# ProtoStack_H750VBT.net
KiCad netlist of a schematic drawn in Altium Designer
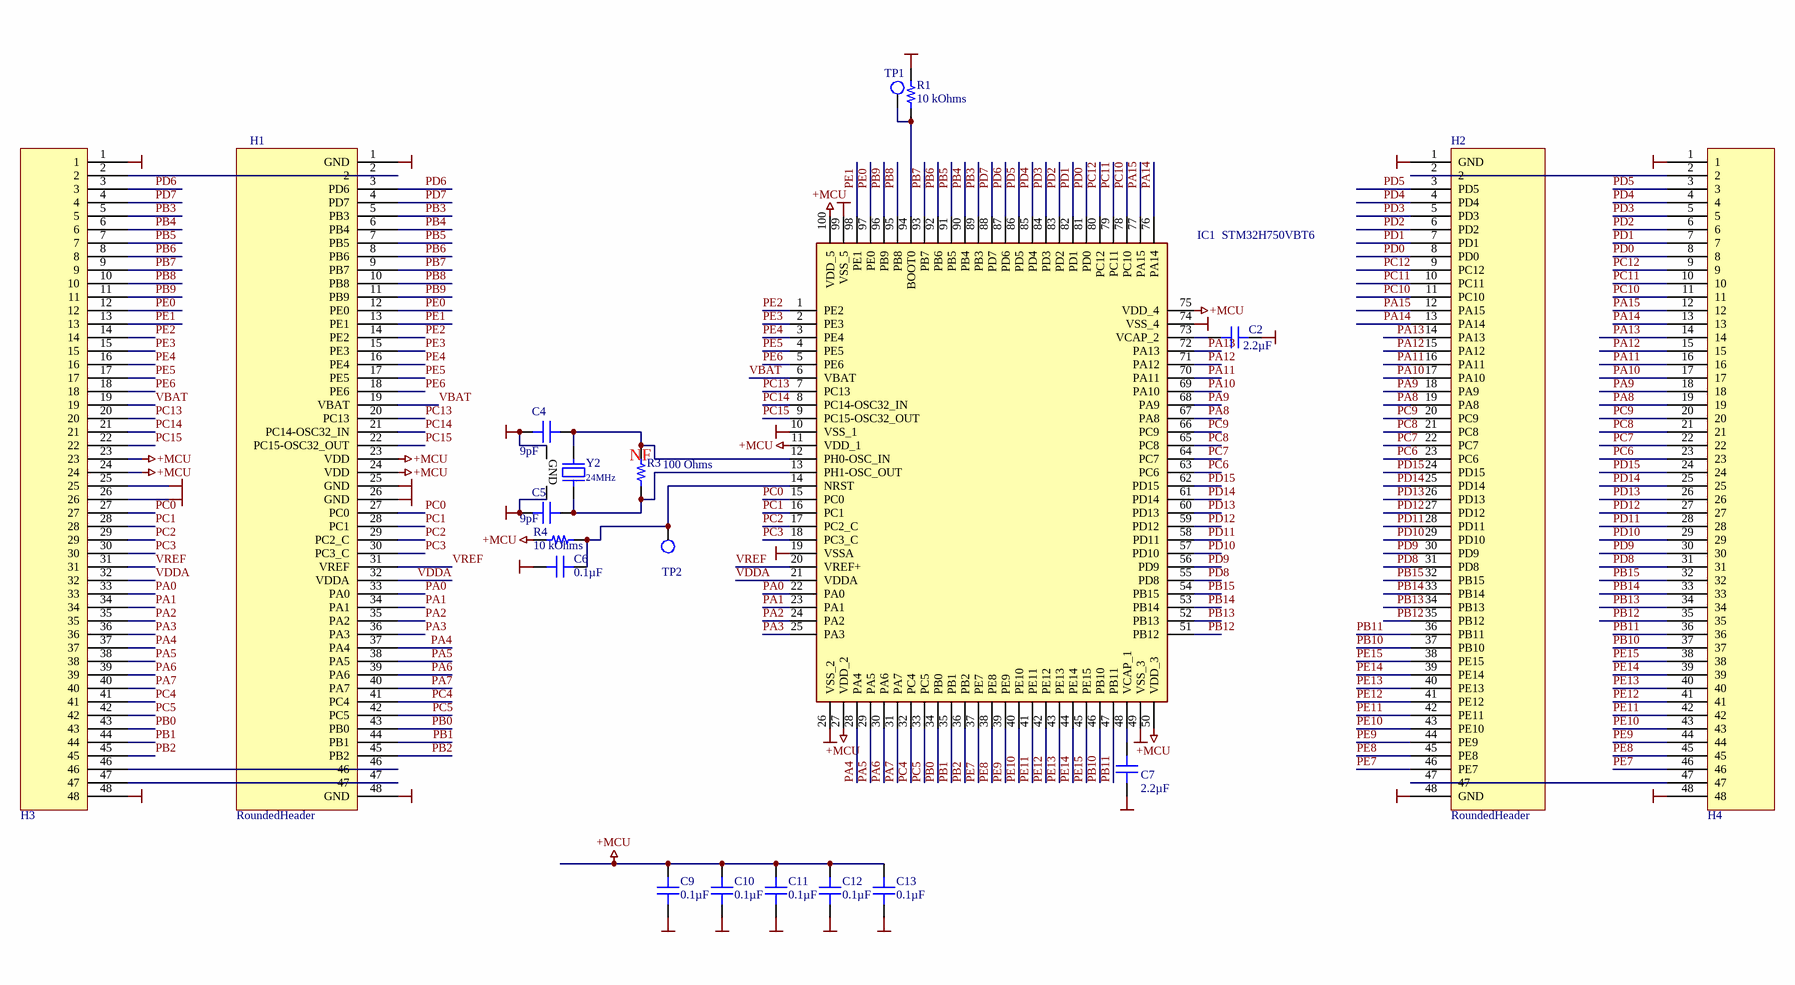
[diagram p0: ProtoStack_H750VBT.SchDoc]

(export (version "E")
  (design (tool "Eeschema 10.0.6"))
  (components
    (comp (ref "C2")
      (value "2.2µF")
      (footprint "CAP 0805_2012")
      (description "CAP CER 2.2UF 10V X7R 0805")
      (fields (field (name "PART NUMBER") "C0805C225K8RACTU") (field (name "MANUFACTURER") "KEMET"))
      (libsource (lib "Celestial Altium Library - altium_library") (part "Capacitor"))
    )
    (comp (ref "C4")
      (value "9pF")
      (footprint "CAP 0805_2012")
      (description "CAP CER 9PF 250V C0G/NP0 0805")
      (fields (field (name "PART NUMBER") "CBR08C909CAGAC") (field (name "MANUFACTURER") "KEMET"))
      (libsource (lib "Celestial Altium Library - altium_library") (part "Capacitor"))
    )
    (comp (ref "C5")
      (value "9pF")
      (footprint "CAP 0805_2012")
      (description "CAP CER 9PF 250V C0G/NP0 0805")
      (fields (field (name "PART NUMBER") "CBR08C909CAGAC") (field (name "MANUFACTURER") "KEMET"))
      (libsource (lib "Celestial Altium Library - altium_library") (part "Capacitor"))
    )
    (comp (ref "C6")
      (value "0.1µF")
      (footprint "CAP 0402_1005")
      (description "CAP CER 0.1UF 16V X7R 0402")
      (fields (field (name "PART NUMBER") "C0402C104K4RACAUTO") (field (name "MANUFACTURER") "KEMET"))
      (libsource (lib "Celestial Altium Library - altium_library") (part "Capacitor"))
    )
    (comp (ref "C7")
      (value "2.2µF")
      (footprint "CAP 0805_2012")
      (description "CAP CER 2.2UF 10V X7R 0805")
      (fields (field (name "PART NUMBER") "C0805C225K8RACTU") (field (name "MANUFACTURER") "KEMET"))
      (libsource (lib "Celestial Altium Library - altium_library") (part "Capacitor"))
    )
    (comp (ref "C9")
      (value "0.1µF")
      (footprint "CAP 0402_1005")
      (description "CAP CER 0.1UF 16V X7R 0402")
      (fields (field (name "PART NUMBER") "C0402C104K4RACAUTO") (field (name "MANUFACTURER") "KEMET"))
      (libsource (lib "Celestial Altium Library - altium_library") (part "Capacitor"))
    )
    (comp (ref "C10")
      (value "0.1µF")
      (footprint "CAP 0402_1005")
      (description "CAP CER 0.1UF 16V X7R 0402")
      (fields (field (name "PART NUMBER") "C0402C104K4RACAUTO") (field (name "MANUFACTURER") "KEMET"))
      (libsource (lib "Celestial Altium Library - altium_library") (part "Capacitor"))
    )
    (comp (ref "C11")
      (value "0.1µF")
      (footprint "CAP 0402_1005")
      (description "CAP CER 0.1UF 16V X7R 0402")
      (fields (field (name "PART NUMBER") "C0402C104K4RACAUTO") (field (name "MANUFACTURER") "KEMET"))
      (libsource (lib "Celestial Altium Library - altium_library") (part "Capacitor"))
    )
    (comp (ref "C12")
      (value "0.1µF")
      (footprint "CAP 0402_1005")
      (description "CAP CER 0.1UF 16V X7R 0402")
      (fields (field (name "PART NUMBER") "C0402C104K4RACAUTO") (field (name "MANUFACTURER") "KEMET"))
      (libsource (lib "Celestial Altium Library - altium_library") (part "Capacitor"))
    )
    (comp (ref "C13")
      (value "0.1µF")
      (footprint "CAP 0402_1005")
      (description "CAP CER 0.1UF 16V X7R 0402")
      (fields (field (name "PART NUMBER") "C0402C104K4RACAUTO") (field (name "MANUFACTURER") "KEMET"))
      (libsource (lib "Celestial Altium Library - altium_library") (part "Capacitor"))
    )
    (comp (ref "H1")
      (value "RoundedHeader")
      (footprint "ProtoStack_H750VBT:HeaderDtack_48")
      (libsource (lib "ProtoStack_H750VBT") (part "HeaderStack_48_H7VB50_L"))
    )
    (comp (ref "H2")
      (value "RoundedHeader")
      (footprint "ProtoStack_H750VBT:HeaderDtack_48")
      (libsource (lib "ProtoStack_H750VBT") (part "HeaderStack_48_H7VB50_R"))
    )
    (comp (ref "H3")
      (value "male pin header")
      (footprint "ProtoStack_H750VBT:Header_48")
      (libsource (lib "") (part "Header_48_1"))
    )
    (comp (ref "H4")
      (value "male pin header")
      (footprint "ProtoStack_H750VBT:Header_48")
      (libsource (lib "ProtoStack_H750VBT") (part "Header_48"))
    )
    (comp (ref "IC1")
      (value "STM32H750VBT6")
      (footprint "ProtoStack_H750VBT:QFP50P1600X1600X160-100N")
      (description "Integrated Circuit")
      (fields (field (name "MOUSER PART NUMBER") "511-STM32H750VBT6"))
      (libsource (lib "ProtoStack_H750VBT") (part "STM32H750VBT6"))
    )
    (comp (ref "R1")
      (value "10 kOhms")
      (footprint "RES 0603_1608")
      (description "RES SMD 10K OHM 1% 1/10W 0603")
      (fields (field (name "PART NUMBER") "RT0603FRE0710KL") (field (name "MANUFACTURER") "Yageo"))
      (libsource (lib "Celestial Altium Library - altium_library") (part "Resistor"))
    )
    (comp (ref "R3")
      (value "100 Ohms")
      (footprint "RES 0402_1005")
      (description "RES SMD 100 OHM 1% 1/16W 0402")
      (fields (field (name "PART NUMBER") "RT0402FRE07100RL") (field (name "MANUFACTURER") "Yageo"))
      (libsource (lib "Celestial Altium Library - altium_library") (part "Resistor"))
    )
    (comp (ref "R4")
      (value "10 kOhms")
      (footprint "RES 0603_1608")
      (description "RES SMD 10K OHM 1% 1/10W 0603")
      (fields (field (name "PART NUMBER") "RT0603FRE0710KL") (field (name "MANUFACTURER") "Yageo"))
      (libsource (lib "Celestial Altium Library - altium_library") (part "Resistor"))
    )
    (comp (ref "TP1")
      (value "TestPoint")
      (footprint "ProtoStack_H750VBT:TESTPOINT_VIA")
      (libsource (lib "ProtoStack_H750VBT") (part "TestPoint"))
    )
    (comp (ref "TP2")
      (value "NRST")
      (footprint "ProtoStack_H750VBT:TESTPOINT")
      (libsource (lib "ProtoStack_H750VBT") (part "TestPoint"))
    )
    (comp (ref "Y2")
      (value "24MHz")
      (footprint "NDK NX3225SA")
      (description "CRYSTAL 24MHZ 9PF SMD")
      (fields
        (field (name "PART NUMBER") "NX3225SA-24MHZ-EXS00A-CS07532")
        (field (name "MANUFACTURER") "NDK America, Inc.")
      )
      (libsource (lib "Celestial Altium Library - altium_library") (part "NDK Crystal NX3225SA"))
    )
  )
  (nets
    (net (code "1") (name "+MCU") (class "Default")
      (node (ref "C10") (pin "1") (pinfunction "1_1") (pintype "passive"))
      (node (ref "C11") (pin "1") (pinfunction "1_1") (pintype "passive"))
      (node (ref "C12") (pin "1") (pinfunction "1_1") (pintype "passive"))
      (node (ref "C13") (pin "1") (pinfunction "1_1") (pintype "passive"))
      (node (ref "C9") (pin "1") (pinfunction "1_1") (pintype "passive"))
      (node (ref "H1") (pin "23") (pinfunction "VDD_23") (pintype "passive"))
      (node (ref "H1") (pin "24") (pinfunction "VDD_24") (pintype "passive"))
      (node (ref "H3") (pin "23") (pinfunction "23_23") (pintype "passive"))
      (node (ref "H3") (pin "24") (pinfunction "24_24") (pintype "passive"))
      (node (ref "IC1") (pin "100") (pinfunction "VDD_5_100") (pintype "passive"))
      (node (ref "IC1") (pin "11") (pinfunction "VDD_1_11") (pintype "passive"))
      (node (ref "IC1") (pin "27") (pinfunction "VDD_2_27") (pintype "passive"))
      (node (ref "IC1") (pin "50") (pinfunction "VDD_3_50") (pintype "passive"))
      (node (ref "IC1") (pin "75") (pinfunction "VDD_4_75") (pintype "passive"))
      (node (ref "R4") (pin "1") (pinfunction "1_1") (pintype "passive"))
    )
    (net (code "2") (name "/PA0") (class "Default")
      (node (ref "H1") (pin "33") (pinfunction "PA0_33") (pintype "passive"))
      (node (ref "H3") (pin "33") (pinfunction "33_33") (pintype "passive"))
      (node (ref "IC1") (pin "22") (pinfunction "PA0_22") (pintype "passive"))
    )
    (net (code "3") (name "/PA1") (class "Default")
      (node (ref "H1") (pin "34") (pinfunction "PA1_34") (pintype "passive"))
      (node (ref "H3") (pin "34") (pinfunction "34_34") (pintype "passive"))
      (node (ref "IC1") (pin "23") (pinfunction "PA1_23") (pintype "passive"))
    )
    (net (code "4") (name "/PA2") (class "Default")
      (node (ref "H1") (pin "35") (pinfunction "PA2_35") (pintype "passive"))
      (node (ref "H3") (pin "35") (pinfunction "35_35") (pintype "passive"))
      (node (ref "IC1") (pin "24") (pinfunction "PA2_24") (pintype "passive"))
    )
    (net (code "5") (name "/PA3") (class "Default")
      (node (ref "H1") (pin "36") (pinfunction "PA3_36") (pintype "passive"))
      (node (ref "H3") (pin "36") (pinfunction "36_36") (pintype "passive"))
      (node (ref "IC1") (pin "25") (pinfunction "PA3_25") (pintype "passive"))
    )
    (net (code "6") (name "/PA4") (class "Default")
      (node (ref "H1") (pin "37") (pinfunction "PA4_37") (pintype "passive"))
      (node (ref "H3") (pin "37") (pinfunction "37_37") (pintype "passive"))
      (node (ref "IC1") (pin "28") (pinfunction "PA4_28") (pintype "passive"))
    )
    (net (code "7") (name "/PA5") (class "Default")
      (node (ref "H1") (pin "38") (pinfunction "PA5_38") (pintype "passive"))
      (node (ref "H3") (pin "38") (pinfunction "38_38") (pintype "passive"))
      (node (ref "IC1") (pin "29") (pinfunction "PA5_29") (pintype "passive"))
    )
    (net (code "8") (name "/PA6") (class "Default")
      (node (ref "H1") (pin "39") (pinfunction "PA6_39") (pintype "passive"))
      (node (ref "H3") (pin "39") (pinfunction "39_39") (pintype "passive"))
      (node (ref "IC1") (pin "30") (pinfunction "PA6_30") (pintype "passive"))
    )
    (net (code "9") (name "/PA7") (class "Default")
      (node (ref "H1") (pin "40") (pinfunction "PA7_40") (pintype "passive"))
      (node (ref "H3") (pin "40") (pinfunction "40_40") (pintype "passive"))
      (node (ref "IC1") (pin "31") (pinfunction "PA7_31") (pintype "passive"))
    )
    (net (code "10") (name "/PA8") (class "Default")
      (node (ref "H2") (pin "19") (pinfunction "PA8_19") (pintype "passive"))
      (node (ref "H4") (pin "19") (pinfunction "19_19") (pintype "passive"))
      (node (ref "IC1") (pin "67") (pinfunction "PA8_67") (pintype "passive"))
    )
    (net (code "11") (name "/PA9") (class "Default")
      (node (ref "H2") (pin "18") (pinfunction "PA9_18") (pintype "passive"))
      (node (ref "H4") (pin "18") (pinfunction "18_18") (pintype "passive"))
      (node (ref "IC1") (pin "68") (pinfunction "PA9_68") (pintype "passive"))
    )
    (net (code "12") (name "/PA10") (class "Default")
      (node (ref "H2") (pin "17") (pinfunction "PA10_17") (pintype "passive"))
      (node (ref "H4") (pin "17") (pinfunction "17_17") (pintype "passive"))
      (node (ref "IC1") (pin "69") (pinfunction "PA10_69") (pintype "passive"))
    )
    (net (code "13") (name "/PA11") (class "Default")
      (node (ref "H2") (pin "16") (pinfunction "PA11_16") (pintype "passive"))
      (node (ref "H4") (pin "16") (pinfunction "16_16") (pintype "passive"))
      (node (ref "IC1") (pin "70") (pinfunction "PA11_70") (pintype "passive"))
    )
    (net (code "14") (name "/PA12") (class "Default")
      (node (ref "H2") (pin "15") (pinfunction "PA12_15") (pintype "passive"))
      (node (ref "H4") (pin "15") (pinfunction "15_15") (pintype "passive"))
      (node (ref "IC1") (pin "71") (pinfunction "PA12_71") (pintype "passive"))
    )
    (net (code "15") (name "/PA13") (class "Default")
      (node (ref "H2") (pin "14") (pinfunction "PA13_14") (pintype "passive"))
      (node (ref "H4") (pin "14") (pinfunction "14_14") (pintype "passive"))
      (node (ref "IC1") (pin "72") (pinfunction "PA13_72") (pintype "passive"))
    )
    (net (code "16") (name "/PA14") (class "Default")
      (node (ref "H2") (pin "13") (pinfunction "PA14_13") (pintype "passive"))
      (node (ref "H4") (pin "13") (pinfunction "13_13") (pintype "passive"))
      (node (ref "IC1") (pin "76") (pinfunction "PA14_76") (pintype "passive"))
    )
    (net (code "17") (name "/PA15") (class "Default")
      (node (ref "H2") (pin "12") (pinfunction "PA15_12") (pintype "passive"))
      (node (ref "H4") (pin "12") (pinfunction "12_12") (pintype "passive"))
      (node (ref "IC1") (pin "77") (pinfunction "PA15_77") (pintype "passive"))
    )
    (net (code "18") (name "/PB0") (class "Default")
      (node (ref "H1") (pin "43") (pinfunction "PB0_43") (pintype "passive"))
      (node (ref "H3") (pin "43") (pinfunction "43_43") (pintype "passive"))
      (node (ref "IC1") (pin "34") (pinfunction "PB0_34") (pintype "passive"))
    )
    (net (code "19") (name "/PB1") (class "Default")
      (node (ref "H1") (pin "44") (pinfunction "PB1_44") (pintype "passive"))
      (node (ref "H3") (pin "44") (pinfunction "44_44") (pintype "passive"))
      (node (ref "IC1") (pin "35") (pinfunction "PB1_35") (pintype "passive"))
    )
    (net (code "20") (name "/PB2") (class "Default")
      (node (ref "H1") (pin "45") (pinfunction "PB2_45") (pintype "passive"))
      (node (ref "H3") (pin "45") (pinfunction "45_45") (pintype "passive"))
      (node (ref "IC1") (pin "36") (pinfunction "PB2_36") (pintype "passive"))
    )
    (net (code "21") (name "/PB3") (class "Default")
      (node (ref "H1") (pin "5") (pinfunction "PB3_5") (pintype "passive"))
      (node (ref "H3") (pin "5") (pinfunction "5_5") (pintype "passive"))
      (node (ref "IC1") (pin "89") (pinfunction "PB3_89") (pintype "passive"))
    )
    (net (code "22") (name "/PB4") (class "Default")
      (node (ref "H1") (pin "6") (pinfunction "PB4_6") (pintype "passive"))
      (node (ref "H3") (pin "6") (pinfunction "6_6") (pintype "passive"))
      (node (ref "IC1") (pin "90") (pinfunction "PB4_90") (pintype "passive"))
    )
    (net (code "23") (name "/PB5") (class "Default")
      (node (ref "H1") (pin "7") (pinfunction "PB5_7") (pintype "passive"))
      (node (ref "H3") (pin "7") (pinfunction "7_7") (pintype "passive"))
      (node (ref "IC1") (pin "91") (pinfunction "PB5_91") (pintype "passive"))
    )
    (net (code "24") (name "/PB6") (class "Default")
      (node (ref "H1") (pin "8") (pinfunction "PB6_8") (pintype "passive"))
      (node (ref "H3") (pin "8") (pinfunction "8_8") (pintype "passive"))
      (node (ref "IC1") (pin "92") (pinfunction "PB6_92") (pintype "passive"))
    )
    (net (code "25") (name "/PB7") (class "Default")
      (node (ref "H1") (pin "9") (pinfunction "PB7_9") (pintype "passive"))
      (node (ref "H3") (pin "9") (pinfunction "9_9") (pintype "passive"))
      (node (ref "IC1") (pin "93") (pinfunction "PB7_93") (pintype "passive"))
    )
    (net (code "26") (name "/PB8") (class "Default")
      (node (ref "H1") (pin "10") (pinfunction "PB8_10") (pintype "passive"))
      (node (ref "H3") (pin "10") (pinfunction "10_10") (pintype "passive"))
      (node (ref "IC1") (pin "95") (pinfunction "PB8_95") (pintype "passive"))
    )
    (net (code "27") (name "/PB9") (class "Default")
      (node (ref "H1") (pin "11") (pinfunction "PB9_11") (pintype "passive"))
      (node (ref "H3") (pin "11") (pinfunction "11_11") (pintype "passive"))
      (node (ref "IC1") (pin "96") (pinfunction "PB9_96") (pintype "passive"))
    )
    (net (code "28") (name "/PB10") (class "Default")
      (node (ref "H2") (pin "37") (pinfunction "PB10_37") (pintype "passive"))
      (node (ref "H4") (pin "37") (pinfunction "37_37") (pintype "passive"))
      (node (ref "IC1") (pin "46") (pinfunction "PB10_46") (pintype "passive"))
    )
    (net (code "29") (name "/PB11") (class "Default")
      (node (ref "H2") (pin "36") (pinfunction "PB11_36") (pintype "passive"))
      (node (ref "H4") (pin "36") (pinfunction "36_36") (pintype "passive"))
      (node (ref "IC1") (pin "47") (pinfunction "PB11_47") (pintype "passive"))
    )
    (net (code "30") (name "/PB12") (class "Default")
      (node (ref "H2") (pin "35") (pinfunction "PB12_35") (pintype "passive"))
      (node (ref "H4") (pin "35") (pinfunction "35_35") (pintype "passive"))
      (node (ref "IC1") (pin "51") (pinfunction "PB12_51") (pintype "passive"))
    )
    (net (code "31") (name "/PB13") (class "Default")
      (node (ref "H2") (pin "34") (pinfunction "PB13_34") (pintype "passive"))
      (node (ref "H4") (pin "34") (pinfunction "34_34") (pintype "passive"))
      (node (ref "IC1") (pin "52") (pinfunction "PB13_52") (pintype "passive"))
    )
    (net (code "32") (name "/PB14") (class "Default")
      (node (ref "H2") (pin "33") (pinfunction "PB14_33") (pintype "passive"))
      (node (ref "H4") (pin "33") (pinfunction "33_33") (pintype "passive"))
      (node (ref "IC1") (pin "53") (pinfunction "PB14_53") (pintype "passive"))
    )
    (net (code "33") (name "/PB15") (class "Default")
      (node (ref "H2") (pin "32") (pinfunction "PB15_32") (pintype "passive"))
      (node (ref "H4") (pin "32") (pinfunction "32_32") (pintype "passive"))
      (node (ref "IC1") (pin "54") (pinfunction "PB15_54") (pintype "passive"))
    )
    (net (code "34") (name "/PC0") (class "Default")
      (node (ref "H1") (pin "27") (pinfunction "PC0_27") (pintype "passive"))
      (node (ref "H3") (pin "27") (pinfunction "27_27") (pintype "passive"))
      (node (ref "IC1") (pin "15") (pinfunction "PC0_15") (pintype "passive"))
    )
    (net (code "35") (name "/PC1") (class "Default")
      (node (ref "H1") (pin "28") (pinfunction "PC1_28") (pintype "passive"))
      (node (ref "H3") (pin "28") (pinfunction "28_28") (pintype "passive"))
      (node (ref "IC1") (pin "16") (pinfunction "PC1_16") (pintype "passive"))
    )
    (net (code "36") (name "/PC2") (class "Default")
      (node (ref "H1") (pin "29") (pinfunction "PC2_C_29") (pintype "passive"))
      (node (ref "H3") (pin "29") (pinfunction "29_29") (pintype "passive"))
      (node (ref "IC1") (pin "17") (pinfunction "PC2_C_17") (pintype "passive"))
    )
    (net (code "37") (name "/PC3") (class "Default")
      (node (ref "H1") (pin "30") (pinfunction "PC3_C_30") (pintype "passive"))
      (node (ref "H3") (pin "30") (pinfunction "30_30") (pintype "passive"))
      (node (ref "IC1") (pin "18") (pinfunction "PC3_C_18") (pintype "passive"))
    )
    (net (code "38") (name "/PC4") (class "Default")
      (node (ref "H1") (pin "41") (pinfunction "PC4_41") (pintype "passive"))
      (node (ref "H3") (pin "41") (pinfunction "41_41") (pintype "passive"))
      (node (ref "IC1") (pin "32") (pinfunction "PC4_32") (pintype "passive"))
    )
    (net (code "39") (name "/PC5") (class "Default")
      (node (ref "H1") (pin "42") (pinfunction "PC5_42") (pintype "passive"))
      (node (ref "H3") (pin "42") (pinfunction "42_42") (pintype "passive"))
      (node (ref "IC1") (pin "33") (pinfunction "PC5_33") (pintype "passive"))
    )
    (net (code "40") (name "/PC6") (class "Default")
      (node (ref "H2") (pin "23") (pinfunction "PC6_23") (pintype "passive"))
      (node (ref "H4") (pin "23") (pinfunction "23_23") (pintype "passive"))
      (node (ref "IC1") (pin "63") (pinfunction "PC6_63") (pintype "passive"))
    )
    (net (code "41") (name "/PC7") (class "Default")
      (node (ref "H2") (pin "22") (pinfunction "PC7_22") (pintype "passive"))
      (node (ref "H4") (pin "22") (pinfunction "22_22") (pintype "passive"))
      (node (ref "IC1") (pin "64") (pinfunction "PC7_64") (pintype "passive"))
    )
    (net (code "42") (name "/PC8") (class "Default")
      (node (ref "H2") (pin "21") (pinfunction "PC8_21") (pintype "passive"))
      (node (ref "H4") (pin "21") (pinfunction "21_21") (pintype "passive"))
      (node (ref "IC1") (pin "65") (pinfunction "PC8_65") (pintype "passive"))
    )
    (net (code "43") (name "/PC9") (class "Default")
      (node (ref "H2") (pin "20") (pinfunction "PC9_20") (pintype "passive"))
      (node (ref "H4") (pin "20") (pinfunction "20_20") (pintype "passive"))
      (node (ref "IC1") (pin "66") (pinfunction "PC9_66") (pintype "passive"))
    )
    (net (code "44") (name "/PC10") (class "Default")
      (node (ref "H2") (pin "11") (pinfunction "PC10_11") (pintype "passive"))
      (node (ref "H4") (pin "11") (pinfunction "11_11") (pintype "passive"))
      (node (ref "IC1") (pin "78") (pinfunction "PC10_78") (pintype "passive"))
    )
    (net (code "45") (name "/PC11") (class "Default")
      (node (ref "H2") (pin "10") (pinfunction "PC11_10") (pintype "passive"))
      (node (ref "H4") (pin "10") (pinfunction "10_10") (pintype "passive"))
      (node (ref "IC1") (pin "79") (pinfunction "PC11_79") (pintype "passive"))
    )
    (net (code "46") (name "/PC12") (class "Default")
      (node (ref "H2") (pin "9") (pinfunction "PC12_9") (pintype "passive"))
      (node (ref "H4") (pin "9") (pinfunction "9_9") (pintype "passive"))
      (node (ref "IC1") (pin "80") (pinfunction "PC12_80") (pintype "passive"))
    )
    (net (code "47") (name "/PC13") (class "Default")
      (node (ref "H1") (pin "20") (pinfunction "PC13_20") (pintype "passive"))
      (node (ref "H3") (pin "20") (pinfunction "20_20") (pintype "passive"))
      (node (ref "IC1") (pin "7") (pinfunction "PC13_7") (pintype "passive"))
    )
    (net (code "48") (name "/PC14") (class "Default")
      (node (ref "H1") (pin "21") (pinfunction "PC14-OSC32_IN_21") (pintype "passive"))
      (node (ref "H3") (pin "21") (pinfunction "21_21") (pintype "passive"))
      (node (ref "IC1") (pin "8") (pinfunction "PC14-OSC32_IN_8") (pintype "passive"))
    )
    (net (code "49") (name "/PC15") (class "Default")
      (node (ref "H1") (pin "22") (pinfunction "PC15-OSC32_OUT_22") (pintype "passive"))
      (node (ref "H3") (pin "22") (pinfunction "22_22") (pintype "passive"))
      (node (ref "IC1") (pin "9") (pinfunction "PC15-OSC32_OUT_9") (pintype "passive"))
    )
    (net (code "50") (name "/PD0") (class "Default")
      (node (ref "H2") (pin "8") (pinfunction "PD0_8") (pintype "passive"))
      (node (ref "H4") (pin "8") (pinfunction "8_8") (pintype "passive"))
      (node (ref "IC1") (pin "81") (pinfunction "PD0_81") (pintype "passive"))
    )
    (net (code "51") (name "/PD1") (class "Default")
      (node (ref "H2") (pin "7") (pinfunction "PD1_7") (pintype "passive"))
      (node (ref "H4") (pin "7") (pinfunction "7_7") (pintype "passive"))
      (node (ref "IC1") (pin "82") (pinfunction "PD1_82") (pintype "passive"))
    )
    (net (code "52") (name "/PD2") (class "Default")
      (node (ref "H2") (pin "6") (pinfunction "PD2_6") (pintype "passive"))
      (node (ref "H4") (pin "6") (pinfunction "6_6") (pintype "passive"))
      (node (ref "IC1") (pin "83") (pinfunction "PD2_83") (pintype "passive"))
    )
    (net (code "53") (name "/PD3") (class "Default")
      (node (ref "H2") (pin "5") (pinfunction "PD3_5") (pintype "passive"))
      (node (ref "H4") (pin "5") (pinfunction "5_5") (pintype "passive"))
      (node (ref "IC1") (pin "84") (pinfunction "PD3_84") (pintype "passive"))
    )
    (net (code "54") (name "/PD4") (class "Default")
      (node (ref "H2") (pin "4") (pinfunction "PD4_4") (pintype "passive"))
      (node (ref "H4") (pin "4") (pinfunction "4_4") (pintype "passive"))
      (node (ref "IC1") (pin "85") (pinfunction "PD4_85") (pintype "passive"))
    )
    (net (code "55") (name "/PD5") (class "Default")
      (node (ref "H2") (pin "3") (pinfunction "PD5_3") (pintype "passive"))
      (node (ref "H4") (pin "3") (pinfunction "3_3") (pintype "passive"))
      (node (ref "IC1") (pin "86") (pinfunction "PD5_86") (pintype "passive"))
    )
    (net (code "56") (name "/PD6") (class "Default")
      (node (ref "H1") (pin "3") (pinfunction "PD6_3") (pintype "passive"))
      (node (ref "H3") (pin "3") (pinfunction "3_3") (pintype "passive"))
      (node (ref "IC1") (pin "87") (pinfunction "PD6_87") (pintype "passive"))
    )
    (net (code "57") (name "/PD7") (class "Default")
      (node (ref "H1") (pin "4") (pinfunction "PD7_4") (pintype "passive"))
      (node (ref "H3") (pin "4") (pinfunction "4_4") (pintype "passive"))
      (node (ref "IC1") (pin "88") (pinfunction "PD7_88") (pintype "passive"))
    )
    (net (code "58") (name "/PD8") (class "Default")
      (node (ref "H2") (pin "31") (pinfunction "PD8_31") (pintype "passive"))
      (node (ref "H4") (pin "31") (pinfunction "31_31") (pintype "passive"))
      (node (ref "IC1") (pin "55") (pinfunction "PD8_55") (pintype "passive"))
    )
    (net (code "59") (name "/PD9") (class "Default")
      (node (ref "H2") (pin "30") (pinfunction "PD9_30") (pintype "passive"))
      (node (ref "H4") (pin "30") (pinfunction "30_30") (pintype "passive"))
      (node (ref "IC1") (pin "56") (pinfunction "PD9_56") (pintype "passive"))
    )
    (net (code "60") (name "/PD10") (class "Default")
      (node (ref "H2") (pin "29") (pinfunction "PD10_29") (pintype "passive"))
      (node (ref "H4") (pin "29") (pinfunction "29_29") (pintype "passive"))
      (node (ref "IC1") (pin "57") (pinfunction "PD10_57") (pintype "passive"))
    )
    (net (code "61") (name "/PD11") (class "Default")
      (node (ref "H2") (pin "28") (pinfunction "PD11_28") (pintype "passive"))
      (node (ref "H4") (pin "28") (pinfunction "28_28") (pintype "passive"))
      (node (ref "IC1") (pin "58") (pinfunction "PD11_58") (pintype "passive"))
    )
    (net (code "62") (name "/PD12") (class "Default")
      (node (ref "H2") (pin "27") (pinfunction "PD12_27") (pintype "passive"))
      (node (ref "H4") (pin "27") (pinfunction "27_27") (pintype "passive"))
      (node (ref "IC1") (pin "59") (pinfunction "PD12_59") (pintype "passive"))
    )
    (net (code "63") (name "/PD13") (class "Default")
      (node (ref "H2") (pin "26") (pinfunction "PD13_26") (pintype "passive"))
      (node (ref "H4") (pin "26") (pinfunction "26_26") (pintype "passive"))
      (node (ref "IC1") (pin "60") (pinfunction "PD13_60") (pintype "passive"))
    )
    (net (code "64") (name "/PD14") (class "Default")
      (node (ref "H2") (pin "25") (pinfunction "PD14_25") (pintype "passive"))
      (node (ref "H4") (pin "25") (pinfunction "25_25") (pintype "passive"))
      (node (ref "IC1") (pin "61") (pinfunction "PD14_61") (pintype "passive"))
    )
    (net (code "65") (name "/PD15") (class "Default")
      (node (ref "H2") (pin "24") (pinfunction "PD15_24") (pintype "passive"))
      (node (ref "H4") (pin "24") (pinfunction "24_24") (pintype "passive"))
      (node (ref "IC1") (pin "62") (pinfunction "PD15_62") (pintype "passive"))
    )
    (net (code "66") (name "/PE0") (class "Default")
      (node (ref "H1") (pin "12") (pinfunction "PE0_12") (pintype "passive"))
      (node (ref "H3") (pin "12") (pinfunction "12_12") (pintype "passive"))
      (node (ref "IC1") (pin "97") (pinfunction "PE0_97") (pintype "passive"))
    )
    (net (code "67") (name "/PE1") (class "Default")
      (node (ref "H1") (pin "13") (pinfunction "PE1_13") (pintype "passive"))
      (node (ref "H3") (pin "13") (pinfunction "13_13") (pintype "passive"))
      (node (ref "IC1") (pin "98") (pinfunction "PE1_98") (pintype "passive"))
    )
    (net (code "68") (name "/PE2") (class "Default")
      (node (ref "H1") (pin "14") (pinfunction "PE2_14") (pintype "passive"))
      (node (ref "H3") (pin "14") (pinfunction "14_14") (pintype "passive"))
      (node (ref "IC1") (pin "1") (pinfunction "PE2_1") (pintype "passive"))
    )
    (net (code "69") (name "/PE3") (class "Default")
      (node (ref "H1") (pin "15") (pinfunction "PE3_15") (pintype "passive"))
      (node (ref "H3") (pin "15") (pinfunction "15_15") (pintype "passive"))
      (node (ref "IC1") (pin "2") (pinfunction "PE3_2") (pintype "passive"))
    )
    (net (code "70") (name "/PE4") (class "Default")
      (node (ref "H1") (pin "16") (pinfunction "PE4_16") (pintype "passive"))
      (node (ref "H3") (pin "16") (pinfunction "16_16") (pintype "passive"))
      (node (ref "IC1") (pin "3") (pinfunction "PE4_3") (pintype "passive"))
    )
    (net (code "71") (name "/PE5") (class "Default")
      (node (ref "H1") (pin "17") (pinfunction "PE5_17") (pintype "passive"))
      (node (ref "H3") (pin "17") (pinfunction "17_17") (pintype "passive"))
      (node (ref "IC1") (pin "4") (pinfunction "PE5_4") (pintype "passive"))
    )
    (net (code "72") (name "/PE6") (class "Default")
      (node (ref "H1") (pin "18") (pinfunction "PE6_18") (pintype "passive"))
      (node (ref "H3") (pin "18") (pinfunction "18_18") (pintype "passive"))
      (node (ref "IC1") (pin "5") (pinfunction "PE6_5") (pintype "passive"))
    )
    (net (code "73") (name "/PE7") (class "Default")
      (node (ref "H2") (pin "46") (pinfunction "PE7_46") (pintype "passive"))
      (node (ref "H4") (pin "46") (pinfunction "46_46") (pintype "passive"))
      (node (ref "IC1") (pin "37") (pinfunction "PE7_37") (pintype "passive"))
    )
    (net (code "74") (name "/PE8") (class "Default")
      (node (ref "H2") (pin "45") (pinfunction "PE8_45") (pintype "passive"))
      (node (ref "H4") (pin "45") (pinfunction "45_45") (pintype "passive"))
      (node (ref "IC1") (pin "38") (pinfunction "PE8_38") (pintype "passive"))
    )
    (net (code "75") (name "/PE9") (class "Default")
      (node (ref "H2") (pin "44") (pinfunction "PE9_44") (pintype "passive"))
      (node (ref "H4") (pin "44") (pinfunction "44_44") (pintype "passive"))
      (node (ref "IC1") (pin "39") (pinfunction "PE9_39") (pintype "passive"))
    )
    (net (code "76") (name "/PE10") (class "Default")
      (node (ref "H2") (pin "43") (pinfunction "PE10_43") (pintype "passive"))
      (node (ref "H4") (pin "43") (pinfunction "43_43") (pintype "passive"))
      (node (ref "IC1") (pin "40") (pinfunction "PE10_40") (pintype "passive"))
    )
    (net (code "77") (name "/PE11") (class "Default")
      (node (ref "H2") (pin "42") (pinfunction "PE11_42") (pintype "passive"))
      (node (ref "H4") (pin "42") (pinfunction "42_42") (pintype "passive"))
      (node (ref "IC1") (pin "41") (pinfunction "PE11_41") (pintype "passive"))
    )
    (net (code "78") (name "/PE12") (class "Default")
      (node (ref "H2") (pin "41") (pinfunction "PE12_41") (pintype "passive"))
      (node (ref "H4") (pin "41") (pinfunction "41_41") (pintype "passive"))
      (node (ref "IC1") (pin "42") (pinfunction "PE12_42") (pintype "passive"))
    )
    (net (code "79") (name "/PE13") (class "Default")
      (node (ref "H2") (pin "40") (pinfunction "PE13_40") (pintype "passive"))
      (node (ref "H4") (pin "40") (pinfunction "40_40") (pintype "passive"))
      (node (ref "IC1") (pin "43") (pinfunction "PE13_43") (pintype "passive"))
    )
    (net (code "80") (name "/PE14") (class "Default")
      (node (ref "H2") (pin "39") (pinfunction "PE14_39") (pintype "passive"))
      (node (ref "H4") (pin "39") (pinfunction "39_39") (pintype "passive"))
      (node (ref "IC1") (pin "44") (pinfunction "PE14_44") (pintype "passive"))
    )
    (net (code "81") (name "/PE15") (class "Default")
      (node (ref "H2") (pin "38") (pinfunction "PE15_38") (pintype "passive"))
      (node (ref "H4") (pin "38") (pinfunction "38_38") (pintype "passive"))
      (node (ref "IC1") (pin "45") (pinfunction "PE15_45") (pintype "passive"))
    )
    (net (code "82") (name "/VBAT") (class "Default")
      (node (ref "H1") (pin "19") (pinfunction "VBAT_19") (pintype "passive"))
      (node (ref "H3") (pin "19") (pinfunction "19_19") (pintype "passive"))
      (node (ref "IC1") (pin "6") (pinfunction "VBAT_6") (pintype "passive"))
    )
    (net (code "83") (name "/VDDA") (class "Default")
      (node (ref "H1") (pin "32") (pinfunction "VDDA_32") (pintype "passive"))
      (node (ref "H3") (pin "32") (pinfunction "32_32") (pintype "passive"))
      (node (ref "IC1") (pin "21") (pinfunction "VDDA_21") (pintype "passive"))
    )
    (net (code "84") (name "/VREF") (class "Default")
      (node (ref "H1") (pin "31") (pinfunction "VREF_31") (pintype "passive"))
      (node (ref "H3") (pin "31") (pinfunction "31_31") (pintype "passive"))
      (node (ref "IC1") (pin "20") (pinfunction "VREF+_20") (pintype "passive"))
    )
    (net (code "85") (name "GND") (class "Default")
      (node (ref "C10") (pin "2") (pinfunction "2_2") (pintype "passive"))
      (node (ref "C11") (pin "2") (pinfunction "2_2") (pintype "passive"))
      (node (ref "C12") (pin "2") (pinfunction "2_2") (pintype "passive"))
      (node (ref "C13") (pin "2") (pinfunction "2_2") (pintype "passive"))
      (node (ref "C2") (pin "2") (pinfunction "2_2") (pintype "passive"))
      (node (ref "C4") (pin "1") (pinfunction "1_1") (pintype "passive"))
      (node (ref "C5") (pin "1") (pinfunction "1_1") (pintype "passive"))
      (node (ref "C6") (pin "1") (pinfunction "1_1") (pintype "passive"))
      (node (ref "C7") (pin "1") (pinfunction "1_1") (pintype "passive"))
      (node (ref "C9") (pin "2") (pinfunction "2_2") (pintype "passive"))
      (node (ref "H1") (pin "1") (pinfunction "GND_1") (pintype "passive"))
      (node (ref "H1") (pin "25") (pinfunction "GND_25") (pintype "passive"))
      (node (ref "H1") (pin "26") (pinfunction "GND_26") (pintype "passive"))
      (node (ref "H1") (pin "48") (pinfunction "GND_48") (pintype "passive"))
      (node (ref "H2") (pin "1") (pinfunction "GND_1") (pintype "passive"))
      (node (ref "H2") (pin "48") (pinfunction "GND_48") (pintype "passive"))
      (node (ref "H3") (pin "1") (pinfunction "1_1") (pintype "passive"))
      (node (ref "H3") (pin "25") (pinfunction "25_25") (pintype "passive"))
      (node (ref "H3") (pin "26") (pinfunction "26_26") (pintype "passive"))
      (node (ref "H3") (pin "48") (pinfunction "48_48") (pintype "passive"))
      (node (ref "H4") (pin "1") (pinfunction "1_1") (pintype "passive"))
      (node (ref "H4") (pin "48") (pinfunction "48_48") (pintype "passive"))
      (node (ref "IC1") (pin "10") (pinfunction "VSS_1_10") (pintype "passive"))
      (node (ref "IC1") (pin "19") (pinfunction "VSSA_19") (pintype "passive"))
      (node (ref "IC1") (pin "26") (pinfunction "VSS_2_26") (pintype "passive"))
      (node (ref "IC1") (pin "49") (pinfunction "VSS_3_49") (pintype "passive"))
      (node (ref "IC1") (pin "74") (pinfunction "VSS_4_74") (pintype "passive"))
      (node (ref "IC1") (pin "99") (pinfunction "VSS_5_99") (pintype "passive"))
      (node (ref "R1") (pin "2") (pinfunction "2_2") (pintype "passive"))
      (node (ref "Y2") (pin "2") (pinfunction "GND_2") (pintype "passive"))
      (node (ref "Y2") (pin "4") (pinfunction "GND_4") (pintype "passive"))
    )
    (net (code "86") (name "Net-(H1-Pad2)") (class "Default")
      (node (ref "H1") (pin "2") (pinfunction "2_2") (pintype "passive"))
      (node (ref "H3") (pin "2") (pinfunction "2_2") (pintype "passive"))
    )
    (net (code "87") (name "Net-(H1-Pad46)") (class "Default")
      (node (ref "H1") (pin "46") (pinfunction "46_46") (pintype "passive"))
      (node (ref "H3") (pin "46") (pinfunction "46_46") (pintype "passive"))
    )
    (net (code "88") (name "Net-(H1-Pad47)") (class "Default")
      (node (ref "H1") (pin "47") (pinfunction "47_47") (pintype "passive"))
      (node (ref "H3") (pin "47") (pinfunction "47_47") (pintype "passive"))
    )
    (net (code "89") (name "Net-(H2-Pad2)") (class "Default")
      (node (ref "H2") (pin "2") (pinfunction "2_2") (pintype "passive"))
      (node (ref "H4") (pin "2") (pinfunction "2_2") (pintype "passive"))
    )
    (net (code "90") (name "Net-(H2-Pad47)") (class "Default")
      (node (ref "H2") (pin "47") (pinfunction "47_47") (pintype "passive"))
      (node (ref "H4") (pin "47") (pinfunction "47_47") (pintype "passive"))
    )
    (net (code "91") (name "Net-(IC1-BOOT0)") (class "Default")
      (node (ref "IC1") (pin "94") (pinfunction "BOOT0_94") (pintype "passive"))
      (node (ref "R1") (pin "1") (pinfunction "1_1") (pintype "passive"))
      (node (ref "TP1") (pin "1") (pinfunction "12_1") (pintype "passive"))
    )
    (net (code "92") (name "Net-(IC1-NRST)") (class "Default")
      (node (ref "C6") (pin "2") (pinfunction "2_2") (pintype "passive"))
      (node (ref "IC1") (pin "14") (pinfunction "NRST_14") (pintype "passive"))
      (node (ref "R4") (pin "2") (pinfunction "2_2") (pintype "passive"))
      (node (ref "TP2") (pin "1") (pinfunction "12_1") (pintype "passive"))
    )
    (net (code "93") (name "Net-(IC1-PH0-OSC_IN)") (class "Default")
      (node (ref "C4") (pin "2") (pinfunction "2_2") (pintype "passive"))
      (node (ref "IC1") (pin "12") (pinfunction "PH0-OSC_IN_12") (pintype "passive"))
      (node (ref "R3") (pin "2") (pinfunction "2_2") (pintype "passive"))
      (node (ref "Y2") (pin "1") (pinfunction "1_1") (pintype "passive"))
    )
    (net (code "94") (name "Net-(IC1-PH1-OSC_OUT)") (class "Default")
      (node (ref "C5") (pin "2") (pinfunction "2_2") (pintype "passive"))
      (node (ref "IC1") (pin "13") (pinfunction "PH1-OSC_OUT_13") (pintype "passive"))
      (node (ref "R3") (pin "1") (pinfunction "1_1") (pintype "passive"))
      (node (ref "Y2") (pin "3") (pinfunction "3_3") (pintype "passive"))
    )
    (net (code "95") (name "Net-(IC1-VCAP_1)") (class "Default")
      (node (ref "C7") (pin "2") (pinfunction "2_2") (pintype "passive"))
      (node (ref "IC1") (pin "48") (pinfunction "VCAP_1_48") (pintype "passive"))
    )
    (net (code "96") (name "Net-(IC1-VCAP_2)") (class "Default")
      (node (ref "C2") (pin "1") (pinfunction "1_1") (pintype "passive"))
      (node (ref "IC1") (pin "73") (pinfunction "VCAP_2_73") (pintype "passive"))
    )
  )
)
